# PowerShield.net
KiCad netlist of a schematic drawn in EAGLE
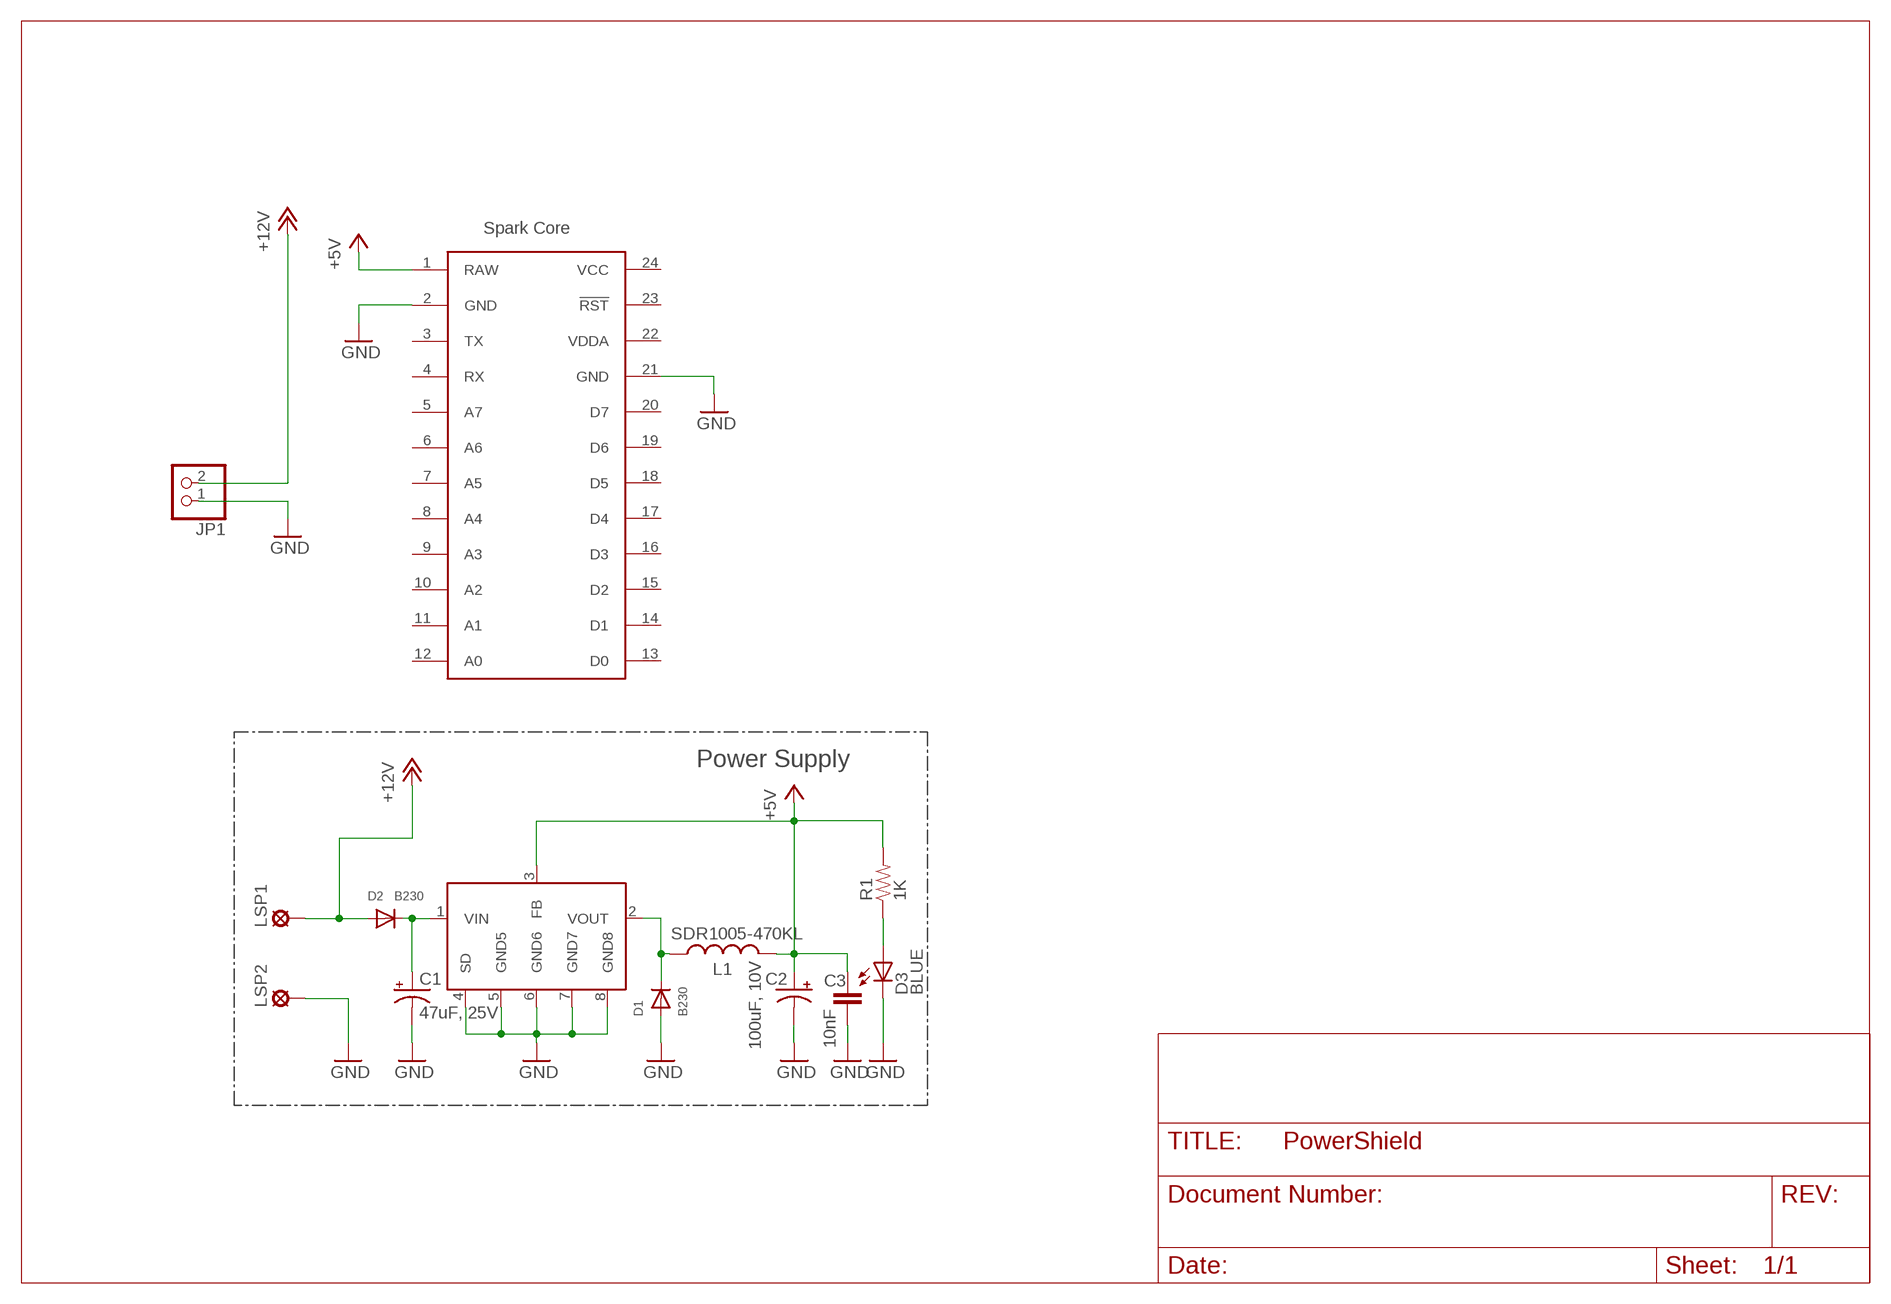
[diagram p0: schematic, sheet 1]

(export (version "E")
  (design (tool "Eeschema 10.0.6"))
  (components
    (comp (ref "C1")
      (value "47uF, 25V")
      (footprint "eagle-import:PANASONIC_D")
      (libsource (lib "eagle-import") (part "CAP_POLD"))
    )
    (comp (ref "C2")
      (value "100uF, 10V")
      (footprint "eagle-import:PANASONIC_D")
      (libsource (lib "eagle-import") (part "CAP_POLD"))
    )
    (comp (ref "C3")
      (value "10nF")
      (footprint "eagle-import:0603-CAP")
      (libsource (lib "eagle-import") (part "CAP0603-CAP"))
    )
    (comp (ref "D1")
      (value "B230")
      (footprint "eagle-import:SMADIODE")
      (libsource (lib "eagle-import") (part "DIODESMA"))
    )
    (comp (ref "D2")
      (value "B230")
      (footprint "eagle-import:SMADIODE")
      (libsource (lib "eagle-import") (part "DIODESMA"))
    )
    (comp (ref "D3")
      (value "BLUE")
      (footprint "eagle-import:LED-0603")
      (libsource (lib "eagle-import") (part "LED0603"))
    )
    (comp (ref "JP1")
      (value "PINHD-1X2")
      (footprint "eagle-import:1X02")
      (libsource (lib "eagle-import") (part "PINHD-1X2"))
    )
    (comp (ref "L1")
      (value "SDR1005-470KL")
      (footprint "eagle-import:INDUCTOR-SDR1005-470KL")
      (libsource (lib "eagle-import") (part "INDUCTOR-SPARKFUN"))
    )
    (comp (ref "LSP1")
      (value "SE14")
      (footprint "eagle-import:SE14")
      (libsource (lib "eagle-import") (part "SE14"))
    )
    (comp (ref "LSP2")
      (value "SE14")
      (footprint "eagle-import:SE14")
      (libsource (lib "eagle-import") (part "SE14"))
    )
    (comp (ref "R1")
      (value "1K")
      (footprint "eagle-import:0603-RES")
      (libsource (lib "eagle-import") (part "RESISTOR0603-RES"))
    )
    (comp (ref "U$2")
      (value "SPARK_CORECORE")
      (footprint "eagle-import:SPARK_CORE")
      (libsource (lib "eagle-import") (part "SPARK_CORECORE"))
    )
    (comp (ref "U1")
      (value "AP1509-50SG-13")
      (footprint "eagle-import:SO08")
      (libsource (lib "eagle-import") (part "AP1509-50SG-13"))
    )
  )
  (nets
    (net (code "1") (name "+5V") (class "Default")
      (node (ref "C2") (pin "+") (pinfunction "+_+") (pintype "passive"))
      (node (ref "C3") (pin "2") (pinfunction "2_2") (pintype "passive"))
      (node (ref "L1") (pin "P$2") (pinfunction "2_P$2") (pintype "passive"))
      (node (ref "R1") (pin "2") (pinfunction "2_2") (pintype "passive"))
      (node (ref "U$2") (pin "1") (pinfunction "RAW_1") (pintype "power_in"))
      (node (ref "U1") (pin "3") (pinfunction "FB_3") (pintype "bidirectional"))
    )
    (net (code "2") (name "+12V") (class "Default")
      (node (ref "D2") (pin "A") (pinfunction "A_A") (pintype "passive"))
      (node (ref "JP1") (pin "2") (pinfunction "2_2") (pintype "passive"))
      (node (ref "LSP1") (pin "MP") (pinfunction "MP_MP") (pintype "passive"))
    )
    (net (code "3") (name "/VCC") (class "Default")
      (node (ref "U$2") (pin "24") (pinfunction "VCC_24") (pintype "power_in"))
    )
    (net (code "4") (name "/VDDA") (class "Default")
      (node (ref "U$2") (pin "22") (pinfunction "VDDA_22") (pintype "power_in"))
    )
    (net (code "5") (name "GND") (class "Default")
      (node (ref "C1") (pin "-") (pinfunction "-_-") (pintype "passive"))
      (node (ref "C2") (pin "-") (pinfunction "-_-") (pintype "passive"))
      (node (ref "C3") (pin "1") (pinfunction "1_1") (pintype "passive"))
      (node (ref "D1") (pin "A") (pinfunction "A_A") (pintype "passive"))
      (node (ref "D3") (pin "C") (pinfunction "C_C") (pintype "passive"))
      (node (ref "JP1") (pin "1") (pinfunction "1_1") (pintype "passive"))
      (node (ref "LSP2") (pin "MP") (pinfunction "MP_MP") (pintype "passive"))
      (node (ref "U$2") (pin "2") (pinfunction "GND_2") (pintype "power_in"))
      (node (ref "U$2") (pin "21") (pinfunction "GND_21") (pintype "power_in"))
      (node (ref "U1") (pin "4") (pinfunction "SD_4") (pintype "bidirectional"))
      (node (ref "U1") (pin "5") (pinfunction "GND5_5") (pintype "bidirectional"))
      (node (ref "U1") (pin "6") (pinfunction "GND6_6") (pintype "bidirectional"))
      (node (ref "U1") (pin "7") (pinfunction "GND7_7") (pintype "bidirectional"))
      (node (ref "U1") (pin "8") (pinfunction "GND8_8") (pintype "bidirectional"))
    )
    (net (code "6") (name "Net-(D3-PadA)") (class "Default")
      (node (ref "D3") (pin "A") (pinfunction "A_A") (pintype "passive"))
      (node (ref "R1") (pin "1") (pinfunction "1_1") (pintype "passive"))
    )
    (net (code "7") (name "Net-(L1-1)") (class "Default")
      (node (ref "D1") (pin "C") (pinfunction "C_C") (pintype "passive"))
      (node (ref "L1") (pin "P$1") (pinfunction "1_P$1") (pintype "passive"))
      (node (ref "U1") (pin "2") (pinfunction "VOUT_2") (pintype "bidirectional"))
    )
    (net (code "8") (name "Net-(U1-VIN)") (class "Default")
      (node (ref "C1") (pin "+") (pinfunction "+_+") (pintype "passive"))
      (node (ref "D2") (pin "C") (pinfunction "C_C") (pintype "passive"))
      (node (ref "U1") (pin "1") (pinfunction "VIN_1") (pintype "bidirectional"))
    )
    (net (code "9") (name "unconnected-(U$2-A0-Pad12)") (class "Default")
      (node (ref "U$2") (pin "12") (pinfunction "A0_12") (pintype "bidirectional"))
    )
    (net (code "10") (name "unconnected-(U$2-A1-Pad11)") (class "Default")
      (node (ref "U$2") (pin "11") (pinfunction "A1_11") (pintype "bidirectional"))
    )
    (net (code "11") (name "unconnected-(U$2-A2-Pad10)") (class "Default")
      (node (ref "U$2") (pin "10") (pinfunction "A2_10") (pintype "bidirectional"))
    )
    (net (code "12") (name "unconnected-(U$2-A3-Pad9)") (class "Default")
      (node (ref "U$2") (pin "9") (pinfunction "A3_9") (pintype "bidirectional"))
    )
    (net (code "13") (name "unconnected-(U$2-A4-Pad8)") (class "Default")
      (node (ref "U$2") (pin "8") (pinfunction "A4_8") (pintype "bidirectional"))
    )
    (net (code "14") (name "unconnected-(U$2-A5-Pad7)") (class "Default")
      (node (ref "U$2") (pin "7") (pinfunction "A5_7") (pintype "bidirectional"))
    )
    (net (code "15") (name "unconnected-(U$2-A6-Pad6)") (class "Default")
      (node (ref "U$2") (pin "6") (pinfunction "A6_6") (pintype "bidirectional"))
    )
    (net (code "16") (name "unconnected-(U$2-A7-Pad5)") (class "Default")
      (node (ref "U$2") (pin "5") (pinfunction "A7_5") (pintype "bidirectional"))
    )
    (net (code "17") (name "unconnected-(U$2-D0-Pad13)") (class "Default")
      (node (ref "U$2") (pin "13") (pinfunction "D0_13") (pintype "bidirectional"))
    )
    (net (code "18") (name "unconnected-(U$2-D1-Pad14)") (class "Default")
      (node (ref "U$2") (pin "14") (pinfunction "D1_14") (pintype "bidirectional"))
    )
    (net (code "19") (name "unconnected-(U$2-D2-Pad15)") (class "Default")
      (node (ref "U$2") (pin "15") (pinfunction "D2_15") (pintype "bidirectional"))
    )
    (net (code "20") (name "unconnected-(U$2-D3-Pad16)") (class "Default")
      (node (ref "U$2") (pin "16") (pinfunction "D3_16") (pintype "bidirectional"))
    )
    (net (code "21") (name "unconnected-(U$2-D4-Pad17)") (class "Default")
      (node (ref "U$2") (pin "17") (pinfunction "D4_17") (pintype "bidirectional"))
    )
    (net (code "22") (name "unconnected-(U$2-D5-Pad18)") (class "Default")
      (node (ref "U$2") (pin "18") (pinfunction "D5_18") (pintype "bidirectional"))
    )
    (net (code "23") (name "unconnected-(U$2-D6-Pad19)") (class "Default")
      (node (ref "U$2") (pin "19") (pinfunction "D6_19") (pintype "bidirectional"))
    )
    (net (code "24") (name "unconnected-(U$2-D7-Pad20)") (class "Default")
      (node (ref "U$2") (pin "20") (pinfunction "D7_20") (pintype "bidirectional"))
    )
    (net (code "25") (name "unconnected-(U$2-RX-Pad4)") (class "Default")
      (node (ref "U$2") (pin "4") (pinfunction "RX_4") (pintype "bidirectional"))
    )
    (net (code "26") (name "unconnected-(U$2-TX-Pad3)") (class "Default")
      (node (ref "U$2") (pin "3") (pinfunction "TX_3") (pintype "bidirectional"))
    )
    (net (code "27") (name "unconnected-(U$2-~{RST}-Pad23)") (class "Default")
      (node (ref "U$2") (pin "23") (pinfunction "~{RST}_23") (pintype "bidirectional"))
    )
  )
)
